# main_board.net
KiCad netlist of a schematic drawn in EAGLE
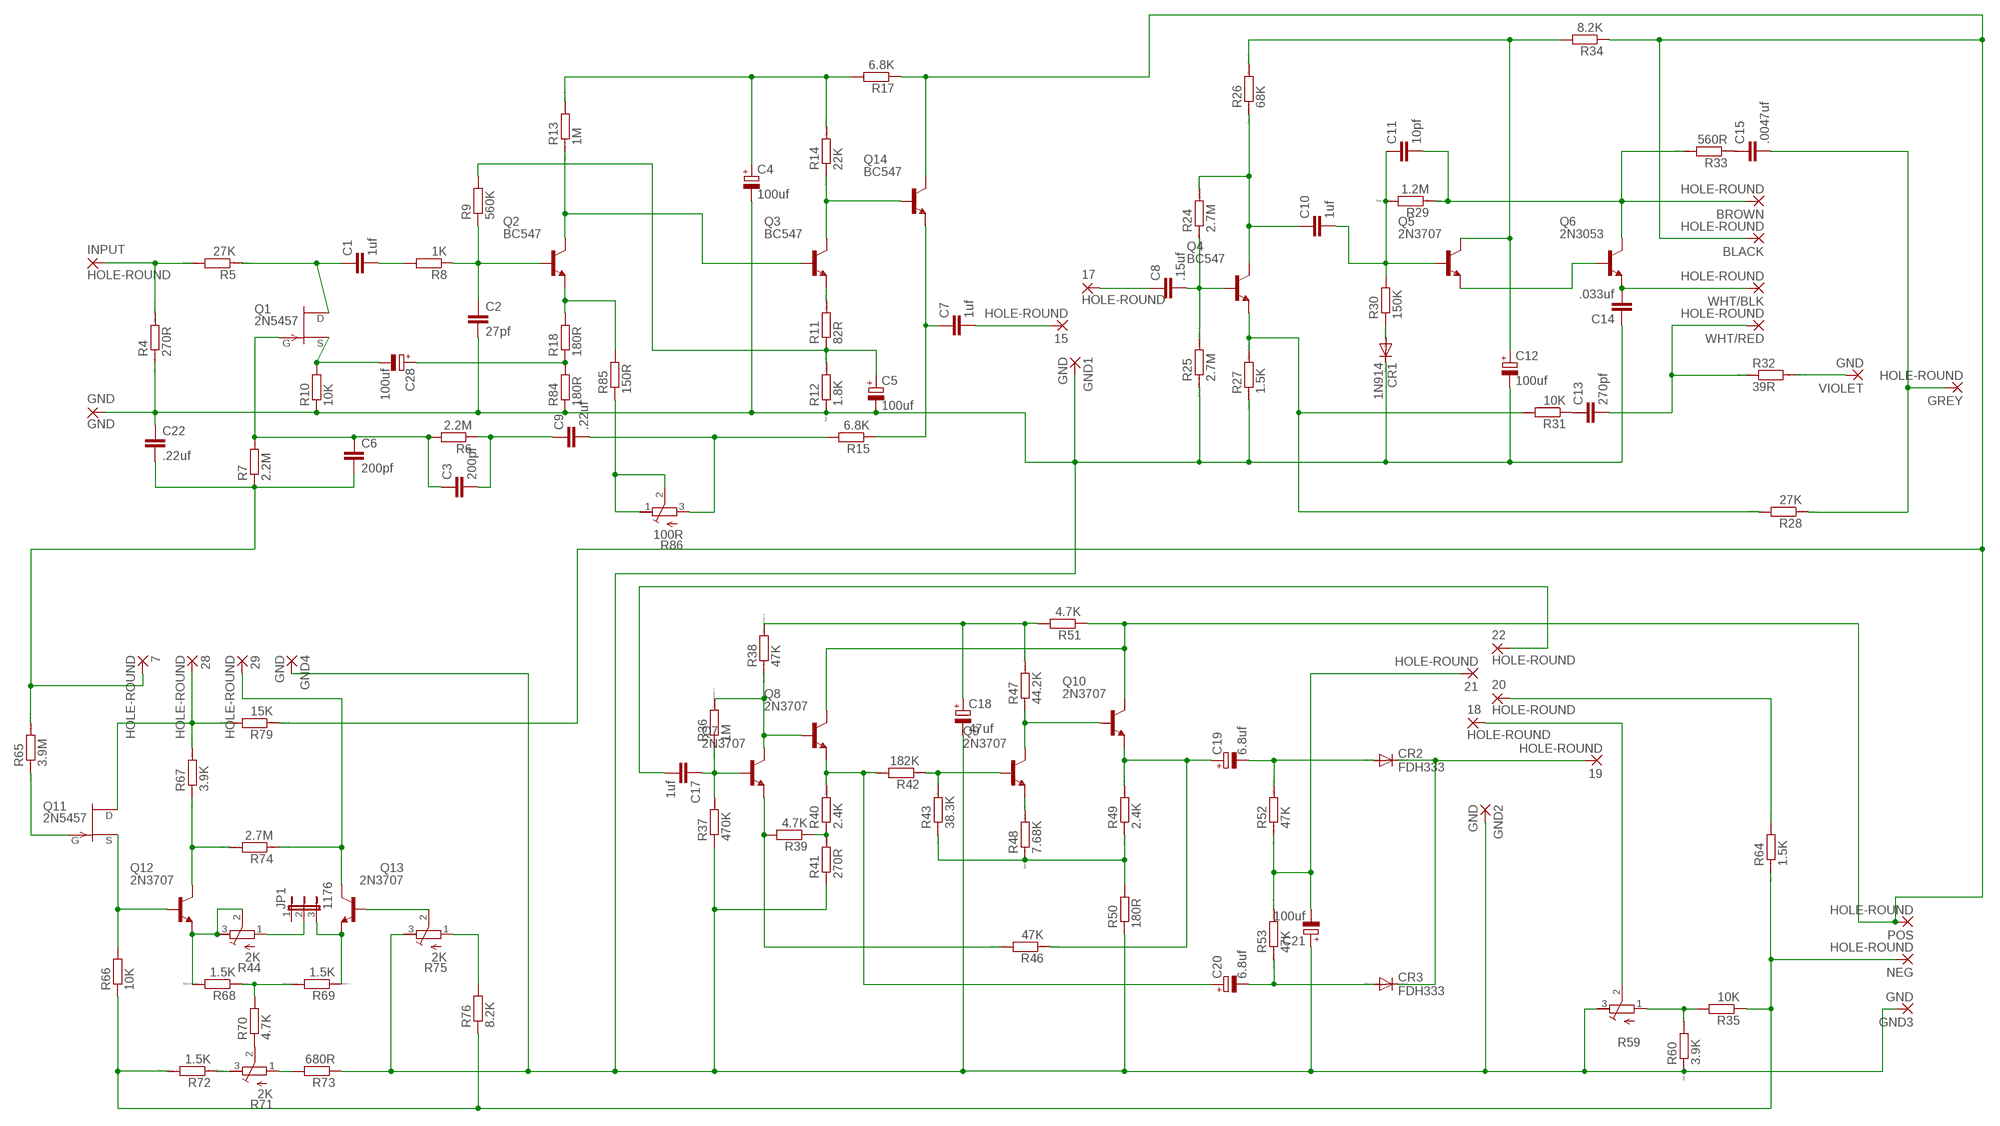
[diagram p0: schematic, sheet 1]

(export (version "E")
  (design (tool "Eeschema 10.0.6"))
  (components
    (comp (ref "7")
      (value "HOLE-ROUND")
      (footprint "eagle-import:HOLE-ROUND")
      (libsource (lib "eagle-import") (part "HOLE-ROUND"))
    )
    (comp (ref "15")
      (value "HOLE-ROUND")
      (footprint "eagle-import:HOLE-ROUND")
      (libsource (lib "eagle-import") (part "HOLE-ROUND"))
    )
    (comp (ref "17")
      (value "HOLE-ROUND")
      (footprint "eagle-import:HOLE-ROUND")
      (libsource (lib "eagle-import") (part "HOLE-ROUND"))
    )
    (comp (ref "18")
      (value "HOLE-ROUND")
      (footprint "eagle-import:HOLE-ROUND")
      (libsource (lib "eagle-import") (part "HOLE-ROUND"))
    )
    (comp (ref "19")
      (value "HOLE-ROUND")
      (footprint "eagle-import:HOLE-ROUND")
      (libsource (lib "eagle-import") (part "HOLE-ROUND"))
    )
    (comp (ref "20")
      (value "HOLE-ROUND")
      (footprint "eagle-import:HOLE-ROUND")
      (libsource (lib "eagle-import") (part "HOLE-ROUND"))
    )
    (comp (ref "21")
      (value "HOLE-ROUND")
      (footprint "eagle-import:HOLE-ROUND")
      (libsource (lib "eagle-import") (part "HOLE-ROUND"))
    )
    (comp (ref "22")
      (value "HOLE-ROUND")
      (footprint "eagle-import:HOLE-ROUND")
      (libsource (lib "eagle-import") (part "HOLE-ROUND"))
    )
    (comp (ref "28")
      (value "HOLE-ROUND")
      (footprint "eagle-import:HOLE-ROUND")
      (libsource (lib "eagle-import") (part "HOLE-ROUND"))
    )
    (comp (ref "29")
      (value "HOLE-ROUND")
      (footprint "eagle-import:HOLE-ROUND")
      (libsource (lib "eagle-import") (part "HOLE-ROUND"))
    )
    (comp (ref "BLACK")
      (value "HOLE-ROUND")
      (footprint "eagle-import:HOLE-ROUND")
      (libsource (lib "eagle-import") (part "HOLE-ROUND"))
    )
    (comp (ref "BROWN")
      (value "HOLE-ROUND")
      (footprint "eagle-import:HOLE-ROUND")
      (libsource (lib "eagle-import") (part "HOLE-ROUND"))
    )
    (comp (ref "C1")
      (value "1uf")
      (footprint "eagle-import:SQUARE")
      (libsource (lib "eagle-import") (part "C-EU"))
    )
    (comp (ref "C2")
      (value "27pf")
      (footprint "eagle-import:C-EU-ROUND")
      (libsource (lib "eagle-import") (part "C-EU-ROUND"))
    )
    (comp (ref "C3")
      (value "200pf")
      (footprint "eagle-import:C050-024X044")
      (libsource (lib "eagle-import") (part "resistor_C-EU050-024X044"))
    )
    (comp (ref "C4")
      (value "100uf")
      (footprint "eagle-import:ROUND7")
      (libsource (lib "eagle-import") (part "CPOL-EUROUND2"))
    )
    (comp (ref "C5")
      (value "100uf")
      (footprint "eagle-import:ROUND7")
      (libsource (lib "eagle-import") (part "CPOL-EUROUND2"))
    )
    (comp (ref "C6")
      (value "200pf")
      (footprint "eagle-import:C050-024X044")
      (libsource (lib "eagle-import") (part "resistor_C-EU050-024X044"))
    )
    (comp (ref "C7")
      (value "1uf")
      (footprint "eagle-import:SQUARE")
      (libsource (lib "eagle-import") (part "C-EU"))
    )
    (comp (ref "C8")
      (value ".15uf")
      (footprint "eagle-import:C-EU-ROUND")
      (libsource (lib "eagle-import") (part "C-EU-ROUND"))
    )
    (comp (ref "C9")
      (value ".22uf")
      (footprint "eagle-import:C-EU-ROUND")
      (libsource (lib "eagle-import") (part "C-EU-ROUND"))
    )
    (comp (ref "C10")
      (value "1uf")
      (footprint "eagle-import:SQUARE")
      (libsource (lib "eagle-import") (part "C-EU"))
    )
    (comp (ref "C11")
      (value "10pf")
      (footprint "eagle-import:C075-032X103")
      (libsource (lib "eagle-import") (part "C-EU075-032X103"))
    )
    (comp (ref "C12")
      (value "100uf")
      (footprint "eagle-import:ROUND7")
      (libsource (lib "eagle-import") (part "CPOL-EUROUND2"))
    )
    (comp (ref "C13")
      (value "270pf")
      (footprint "eagle-import:C-EU-ROUND")
      (libsource (lib "eagle-import") (part "C-EU-ROUND"))
    )
    (comp (ref "C14")
      (value ".033uf")
      (footprint "eagle-import:C-EU-ROUND")
      (libsource (lib "eagle-import") (part "C-EU-ROUND"))
    )
    (comp (ref "C15")
      (value ".0047uf")
      (footprint "eagle-import:C-EU-ROUND")
      (libsource (lib "eagle-import") (part "C-EU-ROUND"))
    )
    (comp (ref "C17")
      (value "1uf")
      (footprint "eagle-import:SQUARE")
      (libsource (lib "eagle-import") (part "C-EU"))
    )
    (comp (ref "C18")
      (value "47uf")
      (footprint "eagle-import:E2,5-6")
      (libsource (lib "eagle-import") (part "CPOL-EUE2.5-6"))
    )
    (comp (ref "C19")
      (value "6.8uf")
      (footprint "eagle-import:E1,8-4")
      (libsource (lib "eagle-import") (part "CPOL-EUE1.8-4"))
    )
    (comp (ref "C20")
      (value "6.8uf")
      (footprint "eagle-import:E1,8-4")
      (libsource (lib "eagle-import") (part "CPOL-EUE1.8-4"))
    )
    (comp (ref "C21")
      (value "100uf")
      (footprint "eagle-import:ROUND7")
      (libsource (lib "eagle-import") (part "CPOL-EUROUND2"))
    )
    (comp (ref "C22")
      (value ".22uf")
      (footprint "eagle-import:C-EU-ROUND")
      (libsource (lib "eagle-import") (part "C-EU-ROUND"))
    )
    (comp (ref "C28")
      (value "100uf")
      (footprint "eagle-import:ROUND7")
      (libsource (lib "eagle-import") (part "CPOL-EUROUND2"))
    )
    (comp (ref "CR1")
      (value "1N914")
      (footprint "eagle-import:DO41-10")
      (libsource (lib "eagle-import") (part "1N4933"))
    )
    (comp (ref "CR2")
      (value "FDH333")
      (footprint "eagle-import:DO41-10")
      (libsource (lib "eagle-import") (part "1N4933"))
    )
    (comp (ref "CR3")
      (value "FDH333")
      (footprint "eagle-import:DO41-10")
      (libsource (lib "eagle-import") (part "1N4933"))
    )
    (comp (ref "GND")
      (value "GND")
      (footprint "eagle-import:HOLE-SQUARE")
      (libsource (lib "eagle-import") (part "HOLE-SQUARE"))
    )
    (comp (ref "GND1")
      (value "GND")
      (footprint "eagle-import:HOLE-SQUARE")
      (libsource (lib "eagle-import") (part "HOLE-SQUARE"))
    )
    (comp (ref "GND2")
      (value "GND")
      (footprint "eagle-import:HOLE-SQUARE")
      (libsource (lib "eagle-import") (part "HOLE-SQUARE"))
    )
    (comp (ref "GND3")
      (value "GND")
      (footprint "eagle-import:HOLE-SQUARE")
      (libsource (lib "eagle-import") (part "HOLE-SQUARE"))
    )
    (comp (ref "GND4")
      (value "GND")
      (footprint "eagle-import:HOLE-SQUARE")
      (libsource (lib "eagle-import") (part "HOLE-SQUARE"))
    )
    (comp (ref "GREY")
      (value "HOLE-ROUND")
      (footprint "eagle-import:HOLE-ROUND")
      (libsource (lib "eagle-import") (part "HOLE-ROUND"))
    )
    (comp (ref "INPUT")
      (value "HOLE-ROUND")
      (footprint "eagle-import:HOLE-ROUND")
      (libsource (lib "eagle-import") (part "HOLE-ROUND"))
    )
    (comp (ref "JP1")
      (value "1176")
      (footprint "eagle-import:1176")
      (libsource (lib "eagle-import") (part "1176"))
    )
    (comp (ref "NEG")
      (value "HOLE-ROUND")
      (footprint "eagle-import:HOLE-ROUND")
      (libsource (lib "eagle-import") (part "HOLE-ROUND"))
    )
    (comp (ref "POS")
      (value "HOLE-ROUND")
      (footprint "eagle-import:HOLE-ROUND")
      (libsource (lib "eagle-import") (part "HOLE-ROUND"))
    )
    (comp (ref "Q1")
      (value "2N5457")
      (footprint "eagle-import:TO92")
      (libsource (lib "eagle-import") (part "BF245"))
    )
    (comp (ref "Q2")
      (value "BC547")
      (footprint "eagle-import:TO92")
      (libsource (lib "eagle-import") (part "BC547"))
    )
    (comp (ref "Q3")
      (value "BC547")
      (footprint "eagle-import:TO92")
      (libsource (lib "eagle-import") (part "BC547"))
    )
    (comp (ref "Q4")
      (value "BC547")
      (footprint "eagle-import:TO92")
      (libsource (lib "eagle-import") (part "BC547"))
    )
    (comp (ref "Q5")
      (value "2N3707")
      (footprint "eagle-import:TO92")
      (libsource (lib "eagle-import") (part "2N3707"))
    )
    (comp (ref "Q6")
      (value "2N3053")
      (footprint "eagle-import:TO39")
      (libsource (lib "eagle-import") (part "2N3053"))
    )
    (comp (ref "Q7")
      (value "2N3707")
      (footprint "eagle-import:TO92")
      (libsource (lib "eagle-import") (part "2N3707"))
    )
    (comp (ref "Q8")
      (value "2N3707")
      (footprint "eagle-import:TO92")
      (libsource (lib "eagle-import") (part "2N3707"))
    )
    (comp (ref "Q9")
      (value "2N3707")
      (footprint "eagle-import:TO92")
      (libsource (lib "eagle-import") (part "2N3707"))
    )
    (comp (ref "Q10")
      (value "2N3707")
      (footprint "eagle-import:TO92")
      (libsource (lib "eagle-import") (part "2N3707"))
    )
    (comp (ref "Q11")
      (value "2N5457")
      (footprint "eagle-import:TO92")
      (libsource (lib "eagle-import") (part "BF245"))
    )
    (comp (ref "Q12")
      (value "2N3707")
      (footprint "eagle-import:TO92")
      (libsource (lib "eagle-import") (part "2N3707"))
    )
    (comp (ref "Q13")
      (value "2N3707")
      (footprint "eagle-import:TO92")
      (libsource (lib "eagle-import") (part "2N3707"))
    )
    (comp (ref "Q14")
      (value "BC547")
      (footprint "eagle-import:TO92")
      (libsource (lib "eagle-import") (part "BC547"))
    )
    (comp (ref "R4")
      (value "270R")
      (footprint "eagle-import:ROUND")
      (libsource (lib "eagle-import") (part "EURESROUND"))
    )
    (comp (ref "R5")
      (value "27K")
      (footprint "eagle-import:ROUND")
      (libsource (lib "eagle-import") (part "EURESROUND"))
    )
    (comp (ref "R6")
      (value "2.2M")
      (footprint "eagle-import:0207_10")
      (libsource (lib "eagle-import") (part "R-EU_0207/10"))
    )
    (comp (ref "R7")
      (value "2.2M")
      (footprint "eagle-import:0207_10")
      (libsource (lib "eagle-import") (part "R-EU_0207/10"))
    )
    (comp (ref "R8")
      (value "1K")
      (footprint "eagle-import:0207_10")
      (libsource (lib "eagle-import") (part "R-EU_0207/10"))
    )
    (comp (ref "R9")
      (value "560K")
      (footprint "eagle-import:0207_10")
      (libsource (lib "eagle-import") (part "R-EU_0207/10"))
    )
    (comp (ref "R10")
      (value "10K")
      (footprint "eagle-import:0207_10")
      (libsource (lib "eagle-import") (part "R-EU_0207/10"))
    )
    (comp (ref "R11")
      (value "82R")
      (footprint "eagle-import:ROUND")
      (libsource (lib "eagle-import") (part "EURESROUND"))
    )
    (comp (ref "R12")
      (value "1.8K")
      (footprint "eagle-import:ROUND")
      (libsource (lib "eagle-import") (part "EURESROUND"))
    )
    (comp (ref "R13")
      (value "1M")
      (footprint "eagle-import:ROUND")
      (libsource (lib "eagle-import") (part "EURESROUND"))
    )
    (comp (ref "R14")
      (value "22K")
      (footprint "eagle-import:ROUND")
      (libsource (lib "eagle-import") (part "EURESROUND"))
    )
    (comp (ref "R15")
      (value "6.8K")
      (footprint "eagle-import:0207_10")
      (libsource (lib "eagle-import") (part "R-EU_0207/10"))
    )
    (comp (ref "R17")
      (value "6.8K")
      (footprint "eagle-import:0207_10")
      (libsource (lib "eagle-import") (part "R-EU_0207/10"))
    )
    (comp (ref "R18")
      (value "180R")
      (footprint "eagle-import:0207_10")
      (libsource (lib "eagle-import") (part "R-EU_0207/10"))
    )
    (comp (ref "R24")
      (value "2.7M")
      (footprint "eagle-import:ROUND")
      (libsource (lib "eagle-import") (part "EURESROUND"))
    )
    (comp (ref "R25")
      (value "2.7M")
      (footprint "eagle-import:ROUND")
      (libsource (lib "eagle-import") (part "EURESROUND"))
    )
    (comp (ref "R26")
      (value "68K")
      (footprint "eagle-import:ROUND")
      (libsource (lib "eagle-import") (part "EURESROUND"))
    )
    (comp (ref "R27")
      (value "1.5K")
      (footprint "eagle-import:ROUND")
      (libsource (lib "eagle-import") (part "EURESROUND"))
    )
    (comp (ref "R28")
      (value "27K")
      (footprint "eagle-import:ROUND")
      (libsource (lib "eagle-import") (part "EURESROUND"))
    )
    (comp (ref "R29")
      (value "1.2M")
      (footprint "eagle-import:ROUND")
      (libsource (lib "eagle-import") (part "EURESROUND"))
    )
    (comp (ref "R30")
      (value "150K")
      (footprint "eagle-import:0207_10")
      (libsource (lib "eagle-import") (part "R-EU_0207/10"))
    )
    (comp (ref "R31")
      (value "10K")
      (footprint "eagle-import:0207_10")
      (libsource (lib "eagle-import") (part "R-EU_0207/10"))
    )
    (comp (ref "R32")
      (value "39R")
      (footprint "eagle-import:ROUND")
      (libsource (lib "eagle-import") (part "EURESROUND"))
    )
    (comp (ref "R33")
      (value "560R")
      (footprint "eagle-import:ROUND")
      (libsource (lib "eagle-import") (part "EURESROUND"))
    )
    (comp (ref "R34")
      (value "8.2K")
      (footprint "eagle-import:0207_10")
      (libsource (lib "eagle-import") (part "R-EU_0207/10"))
    )
    (comp (ref "R35")
      (value "10K")
      (footprint "eagle-import:0207_10")
      (libsource (lib "eagle-import") (part "R-EU_0207/10"))
    )
    (comp (ref "R36")
      (value "1M")
      (footprint "eagle-import:ROUND")
      (libsource (lib "eagle-import") (part "EURESROUND"))
    )
    (comp (ref "R37")
      (value "470K")
      (footprint "eagle-import:0207_10")
      (libsource (lib "eagle-import") (part "R-EU_0207/10"))
    )
    (comp (ref "R38")
      (value "47K")
      (footprint "eagle-import:ROUND")
      (libsource (lib "eagle-import") (part "EURESROUND"))
    )
    (comp (ref "R39")
      (value "4.7K")
      (footprint "eagle-import:0207_10")
      (libsource (lib "eagle-import") (part "R-EU_0207/10"))
    )
    (comp (ref "R40")
      (value "2.4K")
      (footprint "eagle-import:ROUND")
      (libsource (lib "eagle-import") (part "EURESROUND"))
    )
    (comp (ref "R41")
      (value "270R")
      (footprint "eagle-import:0207_10")
      (libsource (lib "eagle-import") (part "R-EU_0207/10"))
    )
    (comp (ref "R42")
      (value "182K")
      (footprint "eagle-import:ROUND")
      (libsource (lib "eagle-import") (part "EURESROUND"))
    )
    (comp (ref "R43")
      (value "38.3K")
      (footprint "eagle-import:ROUND")
      (libsource (lib "eagle-import") (part "EURESROUND"))
    )
    (comp (ref "R44")
      (value "2K")
      (footprint "eagle-import:RTRIM3296W")
      (libsource (lib "eagle-import") (part "resistor_R-TRIMM3296W"))
    )
    (comp (ref "R46")
      (value "47K")
      (footprint "eagle-import:ROUND")
      (libsource (lib "eagle-import") (part "EURESROUND"))
    )
    (comp (ref "R47")
      (value "44.2K")
      (footprint "eagle-import:ROUND")
      (libsource (lib "eagle-import") (part "EURESROUND"))
    )
    (comp (ref "R48")
      (value "7.68K")
      (footprint "eagle-import:ROUND")
      (libsource (lib "eagle-import") (part "EURESROUND"))
    )
    (comp (ref "R49")
      (value "2.4K")
      (footprint "eagle-import:ROUND")
      (libsource (lib "eagle-import") (part "EURESROUND"))
    )
    (comp (ref "R50")
      (value "180R")
      (footprint "eagle-import:0207_10")
      (libsource (lib "eagle-import") (part "R-EU_0207/10"))
    )
    (comp (ref "R51")
      (value "4.7K")
      (footprint "eagle-import:0207_10")
      (libsource (lib "eagle-import") (part "R-EU_0207/10"))
    )
    (comp (ref "R52")
      (value "47K")
      (footprint "eagle-import:ROUND")
      (libsource (lib "eagle-import") (part "EURESROUND"))
    )
    (comp (ref "R53")
      (value "47K")
      (footprint "eagle-import:ROUND")
      (libsource (lib "eagle-import") (part "EURESROUND"))
    )
    (comp (ref "R59")
      (value "R-TRIMM3296W")
      (footprint "eagle-import:RTRIM3296W")
      (libsource (lib "eagle-import") (part "resistor_R-TRIMM3296W"))
    )
    (comp (ref "R60")
      (value "3.9K")
      (footprint "eagle-import:ROUND")
      (libsource (lib "eagle-import") (part "EURESROUND"))
    )
    (comp (ref "R64")
      (value "1.5K")
      (footprint "eagle-import:ROUND")
      (libsource (lib "eagle-import") (part "EURESROUND"))
    )
    (comp (ref "R65")
      (value "3.9M")
      (footprint "eagle-import:ROUND")
      (libsource (lib "eagle-import") (part "EURESROUND"))
    )
    (comp (ref "R66")
      (value "10K")
      (footprint "eagle-import:0207_10")
      (libsource (lib "eagle-import") (part "R-EU_0207/10"))
    )
    (comp (ref "R67")
      (value "3.9K")
      (footprint "eagle-import:ROUND")
      (libsource (lib "eagle-import") (part "EURESROUND"))
    )
    (comp (ref "R68")
      (value "1.5K")
      (footprint "eagle-import:ROUND")
      (libsource (lib "eagle-import") (part "EURESROUND"))
    )
    (comp (ref "R69")
      (value "1.5K")
      (footprint "eagle-import:ROUND")
      (libsource (lib "eagle-import") (part "EURESROUND"))
    )
    (comp (ref "R70")
      (value "4.7K")
      (footprint "eagle-import:0207_10")
      (libsource (lib "eagle-import") (part "R-EU_0207/10"))
    )
    (comp (ref "R71")
      (value "2K")
      (footprint "eagle-import:RTRIM3296W")
      (libsource (lib "eagle-import") (part "resistor_R-TRIMM3296W"))
    )
    (comp (ref "R72")
      (value "1.5K")
      (footprint "eagle-import:ROUND")
      (libsource (lib "eagle-import") (part "EURESROUND"))
    )
    (comp (ref "R73")
      (value "680R")
      (footprint "eagle-import:0207_10")
      (libsource (lib "eagle-import") (part "R-EU_0207/10"))
    )
    (comp (ref "R74")
      (value "2.7M")
      (footprint "eagle-import:ROUND")
      (libsource (lib "eagle-import") (part "EURESROUND"))
    )
    (comp (ref "R75")
      (value "2K")
      (footprint "eagle-import:RTRIM3296W")
      (libsource (lib "eagle-import") (part "resistor_R-TRIMM3296W"))
    )
    (comp (ref "R76")
      (value "8.2K")
      (footprint "eagle-import:0207_10")
      (libsource (lib "eagle-import") (part "R-EU_0207/10"))
    )
    (comp (ref "R79")
      (value "15K")
      (footprint "eagle-import:ROUND")
      (libsource (lib "eagle-import") (part "EURESROUND"))
    )
    (comp (ref "R84")
      (value "180R")
      (footprint "eagle-import:0207_10")
      (libsource (lib "eagle-import") (part "R-EU_0207/10"))
    )
    (comp (ref "R85")
      (value "150R")
      (footprint "eagle-import:0207_10")
      (libsource (lib "eagle-import") (part "R-EU_0207/10"))
    )
    (comp (ref "R86")
      (value "100R")
      (footprint "eagle-import:RTRIM3339P")
      (libsource (lib "eagle-import") (part "R-TRIMM3339P"))
    )
    (comp (ref "VIOLET")
      (value "GND")
      (footprint "eagle-import:HOLE-SQUARE")
      (libsource (lib "eagle-import") (part "HOLE-SQUARE"))
    )
    (comp (ref "WHT/BLK")
      (value "HOLE-ROUND")
      (footprint "eagle-import:HOLE-ROUND")
      (libsource (lib "eagle-import") (part "HOLE-ROUND"))
    )
    (comp (ref "WHT/RED")
      (value "HOLE-ROUND")
      (footprint "eagle-import:HOLE-ROUND")
      (libsource (lib "eagle-import") (part "HOLE-ROUND"))
    )
  )
  (nets
    (net (code "1") (name "Net-(7-P)") (class "Default")
      (node (ref "7") (pin "1") (pinfunction "P_1") (pintype "passive"))
      (node (ref "C22") (pin "2") (pinfunction "2_2") (pintype "passive"))
      (node (ref "C6") (pin "2") (pinfunction "2_2") (pintype "passive"))
      (node (ref "R65") (pin "P$3") (pinfunction "2_P$3") (pintype "passive"))
      (node (ref "R7") (pin "1") (pinfunction "1_1") (pintype "passive"))
    )
    (net (code "2") (name "Net-(15-P)") (class "Default")
      (node (ref "15") (pin "1") (pinfunction "P_1") (pintype "passive"))
      (node (ref "C7") (pin "2") (pinfunction "2_2") (pintype "passive"))
    )
    (net (code "3") (name "Net-(17-P)") (class "Default")
      (node (ref "17") (pin "1") (pinfunction "P_1") (pintype "passive"))
      (node (ref "C8") (pin "1") (pinfunction "1_1") (pintype "passive"))
    )
    (net (code "4") (name "Net-(18-P)") (class "Default")
      (node (ref "18") (pin "1") (pinfunction "P_1") (pintype "passive"))
      (node (ref "R59") (pin "2") (pinfunction "S_2") (pintype "passive"))
    )
    (net (code "5") (name "Net-(19-P)") (class "Default")
      (node (ref "19") (pin "1") (pinfunction "P_1") (pintype "passive"))
      (node (ref "CR2") (pin "C") (pinfunction "C_C") (pintype "passive"))
      (node (ref "CR3") (pin "C") (pinfunction "C_C") (pintype "passive"))
    )
    (net (code "6") (name "Net-(20-P)") (class "Default")
      (node (ref "20") (pin "1") (pinfunction "P_1") (pintype "passive"))
      (node (ref "R64") (pin "P$3") (pinfunction "2_P$3") (pintype "passive"))
    )
    (net (code "7") (name "Net-(21-P)") (class "Default")
      (node (ref "21") (pin "1") (pinfunction "P_1") (pintype "passive"))
      (node (ref "C21") (pin "-") (pinfunction "-_-") (pintype "passive"))
      (node (ref "R52") (pin "P$1") (pinfunction "1_P$1") (pintype "passive"))
      (node (ref "R53") (pin "P$3") (pinfunction "2_P$3") (pintype "passive"))
    )
    (net (code "8") (name "Net-(22-P)") (class "Default")
      (node (ref "22") (pin "1") (pinfunction "P_1") (pintype "passive"))
      (node (ref "C17") (pin "2") (pinfunction "2_2") (pintype "passive"))
    )
    (net (code "9") (name "Net-(28-P)") (class "Default")
      (node (ref "28") (pin "1") (pinfunction "P_1") (pintype "passive"))
      (node (ref "Q11") (pin "3") (pinfunction "D_3") (pintype "passive"))
      (node (ref "R67") (pin "P$3") (pinfunction "2_P$3") (pintype "passive"))
      (node (ref "R79") (pin "P$3") (pinfunction "2_P$3") (pintype "passive"))
    )
    (net (code "10") (name "Net-(29-P)") (class "Default")
      (node (ref "29") (pin "1") (pinfunction "P_1") (pintype "passive"))
      (node (ref "Q13") (pin "2") (pinfunction "C_2") (pintype "passive"))
      (node (ref "R74") (pin "P$1") (pinfunction "1_P$1") (pintype "passive"))
    )
    (net (code "11") (name "Net-(BLACK-P)") (class "Default")
      (node (ref "BLACK") (pin "1") (pinfunction "P_1") (pintype "passive"))
      (node (ref "POS") (pin "1") (pinfunction "P_1") (pintype "passive"))
      (node (ref "Q10") (pin "2") (pinfunction "C_2") (pintype "passive"))
      (node (ref "Q14") (pin "1") (pinfunction "C_1") (pintype "passive"))
      (node (ref "Q8") (pin "2") (pinfunction "C_2") (pintype "passive"))
      (node (ref "R17") (pin "1") (pinfunction "1_1") (pintype "passive"))
      (node (ref "R34") (pin "1") (pinfunction "1_1") (pintype "passive"))
      (node (ref "R51") (pin "1") (pinfunction "1_1") (pintype "passive"))
      (node (ref "R79") (pin "P$1") (pinfunction "1_P$1") (pintype "passive"))
    )
    (net (code "12") (name "Net-(BROWN-P)") (class "Default")
      (node (ref "BROWN") (pin "1") (pinfunction "P_1") (pintype "passive"))
      (node (ref "C11") (pin "2") (pinfunction "2_2") (pintype "passive"))
      (node (ref "Q6") (pin "3") (pinfunction "C_3") (pintype "passive"))
      (node (ref "R29") (pin "P$1") (pinfunction "1_P$1") (pintype "passive"))
      (node (ref "R33") (pin "P$3") (pinfunction "2_P$3") (pintype "passive"))
    )
    (net (code "13") (name "Net-(C1-Pad2)") (class "Default")
      (node (ref "C1") (pin "2") (pinfunction "2_2") (pintype "passive"))
      (node (ref "R8") (pin "2") (pinfunction "2_2") (pintype "passive"))
    )
    (net (code "14") (name "Net-(C3-Pad2)") (class "Default")
      (node (ref "C3") (pin "2") (pinfunction "2_2") (pintype "passive"))
      (node (ref "C9") (pin "1") (pinfunction "1_1") (pintype "passive"))
      (node (ref "R6") (pin "1") (pinfunction "1_1") (pintype "passive"))
    )
    (net (code "15") (name "Net-(C13-Pad1)") (class "Default")
      (node (ref "C13") (pin "1") (pinfunction "1_1") (pintype "passive"))
      (node (ref "R31") (pin "1") (pinfunction "1_1") (pintype "passive"))
    )
    (net (code "16") (name "Net-(C28-Pad+)") (class "Default")
      (node (ref "C28") (pin "+") (pinfunction "+_+") (pintype "passive"))
      (node (ref "R18") (pin "1") (pinfunction "1_1") (pintype "passive"))
      (node (ref "R84") (pin "2") (pinfunction "2_2") (pintype "passive"))
    )
    (net (code "17") (name "Net-(CR1-PadA)") (class "Default")
      (node (ref "CR1") (pin "A") (pinfunction "A_A") (pintype "passive"))
      (node (ref "R30") (pin "1") (pinfunction "1_1") (pintype "passive"))
    )
    (net (code "18") (name "Net-(GND-P)") (class "Default")
      (node (ref "C12") (pin "-") (pinfunction "-_-") (pintype "passive"))
      (node (ref "C14") (pin "1") (pinfunction "1_1") (pintype "passive"))
      (node (ref "C18") (pin "-") (pinfunction "-_-") (pintype "passive"))
      (node (ref "C2") (pin "2") (pinfunction "2_2") (pintype "passive"))
      (node (ref "C21") (pin "+") (pinfunction "+_+") (pintype "passive"))
      (node (ref "C22") (pin "1") (pinfunction "1_1") (pintype "passive"))
      (node (ref "C4") (pin "-") (pinfunction "-_-") (pintype "passive"))
      (node (ref "C5") (pin "-") (pinfunction "-_-") (pintype "passive"))
      (node (ref "CR1") (pin "C") (pinfunction "C_C") (pintype "passive"))
      (node (ref "GND") (pin "1") (pinfunction "P_1") (pintype "passive"))
      (node (ref "GND1") (pin "1") (pinfunction "P_1") (pintype "passive"))
      (node (ref "GND2") (pin "1") (pinfunction "P_1") (pintype "passive"))
      (node (ref "GND3") (pin "1") (pinfunction "P_1") (pintype "passive"))
      (node (ref "GND4") (pin "1") (pinfunction "P_1") (pintype "passive"))
      (node (ref "R10") (pin "1") (pinfunction "1_1") (pintype "passive"))
      (node (ref "R12") (pin "P$1") (pinfunction "1_P$1") (pintype "passive"))
      (node (ref "R25") (pin "P$1") (pinfunction "1_P$1") (pintype "passive"))
      (node (ref "R27") (pin "P$1") (pinfunction "1_P$1") (pintype "passive"))
      (node (ref "R37") (pin "1") (pinfunction "1_1") (pintype "passive"))
      (node (ref "R4") (pin "P$1") (pinfunction "1_P$1") (pintype "passive"))
      (node (ref "R41") (pin "1") (pinfunction "1_1") (pintype "passive"))
      (node (ref "R50") (pin "1") (pinfunction "1_1") (pintype "passive"))
      (node (ref "R59") (pin "3") (pinfunction "E_3") (pintype "passive"))
      (node (ref "R60") (pin "P$1") (pinfunction "1_P$1") (pintype "passive"))
      (node (ref "R73") (pin "1") (pinfunction "1_1") (pintype "passive"))
      (node (ref "R75") (pin "3") (pinfunction "E_3") (pintype "passive"))
      (node (ref "R84") (pin "1") (pinfunction "1_1") (pintype "passive"))
    )
    (net (code "19") (name "Net-(GREY-P)") (class "Default")
      (node (ref "C15") (pin "2") (pinfunction "2_2") (pintype "passive"))
      (node (ref "GREY") (pin "1") (pinfunction "P_1") (pintype "passive"))
      (node (ref "R28") (pin "P$1") (pinfunction "1_P$1") (pintype "passive"))
    )
    (net (code "20") (name "Net-(INPUT-P)") (class "Default")
      (node (ref "INPUT") (pin "1") (pinfunction "P_1") (pintype "passive"))
      (node (ref "R4") (pin "P$3") (pinfunction "2_P$3") (pintype "passive"))
      (node (ref "R5") (pin "P$3") (pinfunction "2_P$3") (pintype "passive"))
    )
    (net (code "21") (name "Net-(NEG-P)") (class "Default")
      (node (ref "NEG") (pin "1") (pinfunction "P_1") (pintype "passive"))
      (node (ref "R35") (pin "1") (pinfunction "1_1") (pintype "passive"))
      (node (ref "R64") (pin "P$1") (pinfunction "1_P$1") (pintype "passive"))
      (node (ref "R66") (pin "1") (pinfunction "1_1") (pintype "passive"))
      (node (ref "R72") (pin "P$3") (pinfunction "2_P$3") (pintype "passive"))
      (node (ref "R76") (pin "1") (pinfunction "1_1") (pintype "passive"))
    )
    (net (code "22") (name "Net-(Q1-D)") (class "Default")
      (node (ref "C1") (pin "1") (pinfunction "1_1") (pintype "passive"))
      (node (ref "Q1") (pin "3") (pinfunction "D_3") (pintype "passive"))
      (node (ref "R5") (pin "P$1") (pinfunction "1_P$1") (pintype "passive"))
    )
    (net (code "23") (name "Net-(Q1-G)") (class "Default")
      (node (ref "C3") (pin "1") (pinfunction "1_1") (pintype "passive"))
      (node (ref "C6") (pin "1") (pinfunction "1_1") (pintype "passive"))
      (node (ref "Q1") (pin "1") (pinfunction "G_1") (pintype "passive"))
      (node (ref "R6") (pin "2") (pinfunction "2_2") (pintype "passive"))
      (node (ref "R7") (pin "2") (pinfunction "2_2") (pintype "passive"))
    )
    (net (code "24") (name "Net-(Q1-S)") (class "Default")
      (node (ref "C28") (pin "-") (pinfunction "-_-") (pintype "passive"))
      (node (ref "Q1") (pin "2") (pinfunction "S_2") (pintype "passive"))
      (node (ref "R10") (pin "2") (pinfunction "2_2") (pintype "passive"))
    )
    (net (code "25") (name "Net-(Q2-B)") (class "Default")
      (node (ref "C2") (pin "1") (pinfunction "1_1") (pintype "passive"))
      (node (ref "Q2") (pin "2") (pinfunction "B_2") (pintype "passive"))
      (node (ref "R8") (pin "1") (pinfunction "1_1") (pintype "passive"))
      (node (ref "R9") (pin "1") (pinfunction "1_1") (pintype "passive"))
    )
    (net (code "26") (name "Net-(Q2-C)") (class "Default")
      (node (ref "Q2") (pin "1") (pinfunction "C_1") (pintype "passive"))
      (node (ref "Q3") (pin "2") (pinfunction "B_2") (pintype "passive"))
      (node (ref "R13") (pin "P$1") (pinfunction "1_P$1") (pintype "passive"))
    )
    (net (code "27") (name "Net-(Q2-E)") (class "Default")
      (node (ref "Q2") (pin "3") (pinfunction "E_3") (pintype "passive"))
      (node (ref "R18") (pin "2") (pinfunction "2_2") (pintype "passive"))
      (node (ref "R85") (pin "2") (pinfunction "2_2") (pintype "passive"))
    )
    (net (code "28") (name "Net-(Q3-E)") (class "Default")
      (node (ref "Q3") (pin "3") (pinfunction "E_3") (pintype "passive"))
      (node (ref "R11") (pin "P$3") (pinfunction "2_P$3") (pintype "passive"))
    )
    (net (code "29") (name "Net-(Q4-B)") (class "Default")
      (node (ref "C8") (pin "2") (pinfunction "2_2") (pintype "passive"))
      (node (ref "Q4") (pin "2") (pinfunction "B_2") (pintype "passive"))
      (node (ref "R24") (pin "P$1") (pinfunction "1_P$1") (pintype "passive"))
      (node (ref "R25") (pin "P$3") (pinfunction "2_P$3") (pintype "passive"))
    )
    (net (code "30") (name "Net-(Q4-C)") (class "Default")
      (node (ref "C10") (pin "1") (pinfunction "1_1") (pintype "passive"))
      (node (ref "Q4") (pin "1") (pinfunction "C_1") (pintype "passive"))
      (node (ref "R24") (pin "P$3") (pinfunction "2_P$3") (pintype "passive"))
      (node (ref "R26") (pin "P$1") (pinfunction "1_P$1") (pintype "passive"))
    )
    (net (code "31") (name "Net-(Q4-E)") (class "Default")
      (node (ref "Q4") (pin "3") (pinfunction "E_3") (pintype "passive"))
      (node (ref "R27") (pin "P$3") (pinfunction "2_P$3") (pintype "passive"))
      (node (ref "R28") (pin "P$3") (pinfunction "2_P$3") (pintype "passive"))
      (node (ref "R31") (pin "2") (pinfunction "2_2") (pintype "passive"))
    )
    (net (code "32") (name "Net-(Q5-B)") (class "Default")
      (node (ref "C10") (pin "2") (pinfunction "2_2") (pintype "passive"))
      (node (ref "C11") (pin "1") (pinfunction "1_1") (pintype "passive"))
      (node (ref "Q5") (pin "3") (pinfunction "B_3") (pintype "passive"))
      (node (ref "R29") (pin "P$3") (pinfunction "2_P$3") (pintype "passive"))
      (node (ref "R30") (pin "2") (pinfunction "2_2") (pintype "passive"))
    )
    (net (code "33") (name "Net-(Q5-C)") (class "Default")
      (node (ref "C12") (pin "+") (pinfunction "+_+") (pintype "passive"))
      (node (ref "Q5") (pin "2") (pinfunction "C_2") (pintype "passive"))
      (node (ref "R26") (pin "P$3") (pinfunction "2_P$3") (pintype "passive"))
      (node (ref "R34") (pin "2") (pinfunction "2_2") (pintype "passive"))
    )
    (net (code "34") (name "Net-(Q5-E)") (class "Default")
      (node (ref "Q5") (pin "1") (pinfunction "E_1") (pintype "passive"))
      (node (ref "Q6") (pin "2") (pinfunction "B_2") (pintype "passive"))
    )
    (net (code "35") (name "Net-(Q6-E)") (class "Default")
      (node (ref "C14") (pin "2") (pinfunction "2_2") (pintype "passive"))
      (node (ref "Q6") (pin "1") (pinfunction "E_1") (pintype "passive"))
      (node (ref "WHT/BLK") (pin "1") (pinfunction "P_1") (pintype "passive"))
    )
    (net (code "36") (name "Net-(Q7-B)") (class "Default")
      (node (ref "C17") (pin "1") (pinfunction "1_1") (pintype "passive"))
      (node (ref "Q7") (pin "3") (pinfunction "B_3") (pintype "passive"))
      (node (ref "R36") (pin "P$1") (pinfunction "1_P$1") (pintype "passive"))
      (node (ref "R37") (pin "2") (pinfunction "2_2") (pintype "passive"))
    )
    (net (code "37") (name "Net-(Q7-C)") (class "Default")
      (node (ref "Q7") (pin "2") (pinfunction "C_2") (pintype "passive"))
      (node (ref "Q8") (pin "3") (pinfunction "B_3") (pintype "passive"))
      (node (ref "R36") (pin "P$3") (pinfunction "2_P$3") (pintype "passive"))
      (node (ref "R38") (pin "P$1") (pinfunction "1_P$1") (pintype "passive"))
    )
    (net (code "38") (name "Net-(Q7-E)") (class "Default")
      (node (ref "Q7") (pin "1") (pinfunction "E_1") (pintype "passive"))
      (node (ref "R39") (pin "2") (pinfunction "2_2") (pintype "passive"))
      (node (ref "R46") (pin "P$3") (pinfunction "2_P$3") (pintype "passive"))
    )
    (net (code "39") (name "Net-(Q8-E)") (class "Default")
      (node (ref "C20") (pin "+") (pinfunction "+_+") (pintype "passive"))
      (node (ref "Q8") (pin "1") (pinfunction "E_1") (pintype "passive"))
      (node (ref "R40") (pin "P$3") (pinfunction "2_P$3") (pintype "passive"))
      (node (ref "R42") (pin "P$3") (pinfunction "2_P$3") (pintype "passive"))
    )
    (net (code "40") (name "Net-(Q9-B)") (class "Default")
      (node (ref "Q9") (pin "3") (pinfunction "B_3") (pintype "passive"))
      (node (ref "R42") (pin "P$1") (pinfunction "1_P$1") (pintype "passive"))
      (node (ref "R43") (pin "P$3") (pinfunction "2_P$3") (pintype "passive"))
    )
    (net (code "41") (name "Net-(Q9-E)") (class "Default")
      (node (ref "Q9") (pin "1") (pinfunction "E_1") (pintype "passive"))
      (node (ref "R48") (pin "P$3") (pinfunction "2_P$3") (pintype "passive"))
    )
    (net (code "42") (name "Net-(Q10-B)") (class "Default")
      (node (ref "Q10") (pin "3") (pinfunction "B_3") (pintype "passive"))
      (node (ref "Q9") (pin "2") (pinfunction "C_2") (pintype "passive"))
      (node (ref "R47") (pin "P$1") (pinfunction "1_P$1") (pintype "passive"))
    )
    (net (code "43") (name "Net-(Q10-E)") (class "Default")
      (node (ref "C19") (pin "+") (pinfunction "+_+") (pintype "passive"))
      (node (ref "Q10") (pin "1") (pinfunction "E_1") (pintype "passive"))
      (node (ref "R46") (pin "P$1") (pinfunction "1_P$1") (pintype "passive"))
      (node (ref "R49") (pin "P$3") (pinfunction "2_P$3") (pintype "passive"))
    )
    (net (code "44") (name "Net-(Q11-G)") (class "Default")
      (node (ref "Q11") (pin "1") (pinfunction "G_1") (pintype "passive"))
      (node (ref "R65") (pin "P$1") (pinfunction "1_P$1") (pintype "passive"))
    )
    (net (code "45") (name "Net-(Q11-S)") (class "Default")
      (node (ref "Q11") (pin "2") (pinfunction "S_2") (pintype "passive"))
      (node (ref "Q12") (pin "3") (pinfunction "B_3") (pintype "passive"))
      (node (ref "R66") (pin "2") (pinfunction "2_2") (pintype "passive"))
    )
    (net (code "46") (name "Net-(Q12-C)") (class "Default")
      (node (ref "Q12") (pin "2") (pinfunction "C_2") (pintype "passive"))
      (node (ref "R67") (pin "P$1") (pinfunction "1_P$1") (pintype "passive"))
      (node (ref "R74") (pin "P$3") (pinfunction "2_P$3") (pintype "passive"))
    )
    (net (code "47") (name "Net-(Q12-E)") (class "Default")
      (node (ref "Q12") (pin "1") (pinfunction "E_1") (pintype "passive"))
      (node (ref "R44") (pin "2") (pinfunction "S_2") (pintype "passive"))
      (node (ref "R44") (pin "3") (pinfunction "E_3") (pintype "passive"))
      (node (ref "R68") (pin "P$3") (pinfunction "2_P$3") (pintype "passive"))
    )
    (net (code "48") (name "Net-(Q13-B)") (class "Default")
      (node (ref "Q13") (pin "3") (pinfunction "B_3") (pintype "passive"))
      (node (ref "R75") (pin "2") (pinfunction "S_2") (pintype "passive"))
    )
    (net (code "49") (name "Net-(Q13-E)") (class "Default")
      (node (ref "JP1") (pin "3") (pinfunction "3_3") (pintype "passive"))
      (node (ref "Q13") (pin "1") (pinfunction "E_1") (pintype "passive"))
      (node (ref "R69") (pin "P$1") (pinfunction "1_P$1") (pintype "passive"))
    )
    (net (code "50") (name "Net-(Q14-B)") (class "Default")
      (node (ref "Q14") (pin "2") (pinfunction "B_2") (pintype "passive"))
      (node (ref "Q3") (pin "1") (pinfunction "C_1") (pintype "passive"))
      (node (ref "R14") (pin "P$1") (pinfunction "1_P$1") (pintype "passive"))
    )
    (net (code "51") (name "Net-(Q14-E)") (class "Default")
      (node (ref "C7") (pin "1") (pinfunction "1_1") (pintype "passive"))
      (node (ref "Q14") (pin "3") (pinfunction "E_3") (pintype "passive"))
      (node (ref "R15") (pin "1") (pinfunction "1_1") (pintype "passive"))
    )
    (net (code "52") (name "Net-(R11-1)") (class "Default")
      (node (ref "C5") (pin "+") (pinfunction "+_+") (pintype "passive"))
      (node (ref "R11") (pin "P$1") (pinfunction "1_P$1") (pintype "passive"))
      (node (ref "R12") (pin "P$3") (pinfunction "2_P$3") (pintype "passive"))
      (node (ref "R9") (pin "2") (pinfunction "2_2") (pintype "passive"))
    )
    (net (code "53") (name "Net-(R13-2)") (class "Default")
      (node (ref "C4") (pin "+") (pinfunction "+_+") (pintype "passive"))
      (node (ref "R13") (pin "P$3") (pinfunction "2_P$3") (pintype "passive"))
      (node (ref "R14") (pin "P$3") (pinfunction "2_P$3") (pintype "passive"))
      (node (ref "R17") (pin "2") (pinfunction "2_2") (pintype "passive"))
    )
    (net (code "54") (name "Net-(R32-1)") (class "Default")
      (node (ref "C13") (pin "2") (pinfunction "2_2") (pintype "passive"))
      (node (ref "R32") (pin "P$1") (pinfunction "1_P$1") (pintype "passive"))
      (node (ref "WHT/RED") (pin "1") (pinfunction "P_1") (pintype "passive"))
    )
    (net (code "55") (name "Net-(R32-2)") (class "Default")
      (node (ref "R32") (pin "P$3") (pinfunction "2_P$3") (pintype "passive"))
      (node (ref "VIOLET") (pin "1") (pinfunction "P_1") (pintype "passive"))
    )
    (net (code "56") (name "Net-(R33-1)") (class "Default")
      (node (ref "C15") (pin "1") (pinfunction "1_1") (pintype "passive"))
      (node (ref "R33") (pin "P$1") (pinfunction "1_P$1") (pintype "passive"))
    )
    (net (code "57") (name "Net-(R38-2)") (class "Default")
      (node (ref "C18") (pin "+") (pinfunction "+_+") (pintype "passive"))
      (node (ref "R38") (pin "P$3") (pinfunction "2_P$3") (pintype "passive"))
      (node (ref "R47") (pin "P$3") (pinfunction "2_P$3") (pintype "passive"))
      (node (ref "R51") (pin "2") (pinfunction "2_2") (pintype "passive"))
    )
    (net (code "58") (name "Net-(R40-1)") (class "Default")
      (node (ref "R39") (pin "1") (pinfunction "1_1") (pintype "passive"))
      (node (ref "R40") (pin "P$1") (pinfunction "1_P$1") (pintype "passive"))
      (node (ref "R41") (pin "2") (pinfunction "2_2") (pintype "passive"))
    )
    (net (code "59") (name "Net-(R43-1)") (class "Default")
      (node (ref "R43") (pin "P$1") (pinfunction "1_P$1") (pintype "passive"))
      (node (ref "R48") (pin "P$1") (pinfunction "1_P$1") (pintype "passive"))
      (node (ref "R49") (pin "P$1") (pinfunction "1_P$1") (pintype "passive"))
      (node (ref "R50") (pin "2") (pinfunction "2_2") (pintype "passive"))
    )
    (net (code "60") (name "Net-(R44-A)") (class "Default")
      (node (ref "JP1") (pin "2") (pinfunction "2_2") (pintype "passive"))
      (node (ref "R44") (pin "1") (pinfunction "A_1") (pintype "passive"))
    )
    (net (code "61") (name "Net-(R52-2)") (class "Default")
      (node (ref "C19") (pin "-") (pinfunction "-_-") (pintype "passive"))
      (node (ref "CR2") (pin "A") (pinfunction "A_A") (pintype "passive"))
      (node (ref "R52") (pin "P$3") (pinfunction "2_P$3") (pintype "passive"))
    )
    (net (code "62") (name "Net-(R53-1)") (class "Default")
      (node (ref "C20") (pin "-") (pinfunction "-_-") (pintype "passive"))
      (node (ref "CR3") (pin "A") (pinfunction "A_A") (pintype "passive"))
      (node (ref "R53") (pin "P$1") (pinfunction "1_P$1") (pintype "passive"))
    )
    (net (code "63") (name "Net-(R59-A)") (class "Default")
      (node (ref "R35") (pin "2") (pinfunction "2_2") (pintype "passive"))
      (node (ref "R59") (pin "1") (pinfunction "A_1") (pintype "passive"))
      (node (ref "R60") (pin "P$3") (pinfunction "2_P$3") (pintype "passive"))
    )
    (net (code "64") (name "Net-(R68-1)") (class "Default")
      (node (ref "R68") (pin "P$1") (pinfunction "1_P$1") (pintype "passive"))
      (node (ref "R69") (pin "P$3") (pinfunction "2_P$3") (pintype "passive"))
      (node (ref "R70") (pin "2") (pinfunction "2_2") (pintype "passive"))
    )
    (net (code "65") (name "Net-(R71-A)") (class "Default")
      (node (ref "R71") (pin "1") (pinfunction "A_1") (pintype "passive"))
      (node (ref "R73") (pin "2") (pinfunction "2_2") (pintype "passive"))
    )
    (net (code "66") (name "Net-(R71-E)") (class "Default")
      (node (ref "R71") (pin "3") (pinfunction "E_3") (pintype "passive"))
      (node (ref "R72") (pin "P$1") (pinfunction "1_P$1") (pintype "passive"))
    )
    (net (code "67") (name "Net-(R71-S)") (class "Default")
      (node (ref "R70") (pin "1") (pinfunction "1_1") (pintype "passive"))
      (node (ref "R71") (pin "2") (pinfunction "S_2") (pintype "passive"))
    )
    (net (code "68") (name "Net-(R75-A)") (class "Default")
      (node (ref "R75") (pin "1") (pinfunction "A_1") (pintype "passive"))
      (node (ref "R76") (pin "2") (pinfunction "2_2") (pintype "passive"))
    )
    (net (code "69") (name "Net-(R86-A)") (class "Default")
      (node (ref "C9") (pin "2") (pinfunction "2_2") (pintype "passive"))
      (node (ref "R15") (pin "2") (pinfunction "2_2") (pintype "passive"))
      (node (ref "R86") (pin "3") (pinfunction "A_3") (pintype "passive"))
    )
    (net (code "70") (name "Net-(R86-E)") (class "Default")
      (node (ref "R85") (pin "1") (pinfunction "1_1") (pintype "passive"))
      (node (ref "R86") (pin "1") (pinfunction "E_1") (pintype "passive"))
      (node (ref "R86") (pin "2") (pinfunction "S_2") (pintype "passive"))
    )
    (net (code "71") (name "unconnected-(JP1-Pad1)") (class "Default")
      (node (ref "JP1") (pin "1") (pinfunction "1_1") (pintype "passive"))
    )
  )
)
